# 2019_Dashboard_1-29-19.net
KiCad netlist of a schematic drawn in EAGLE
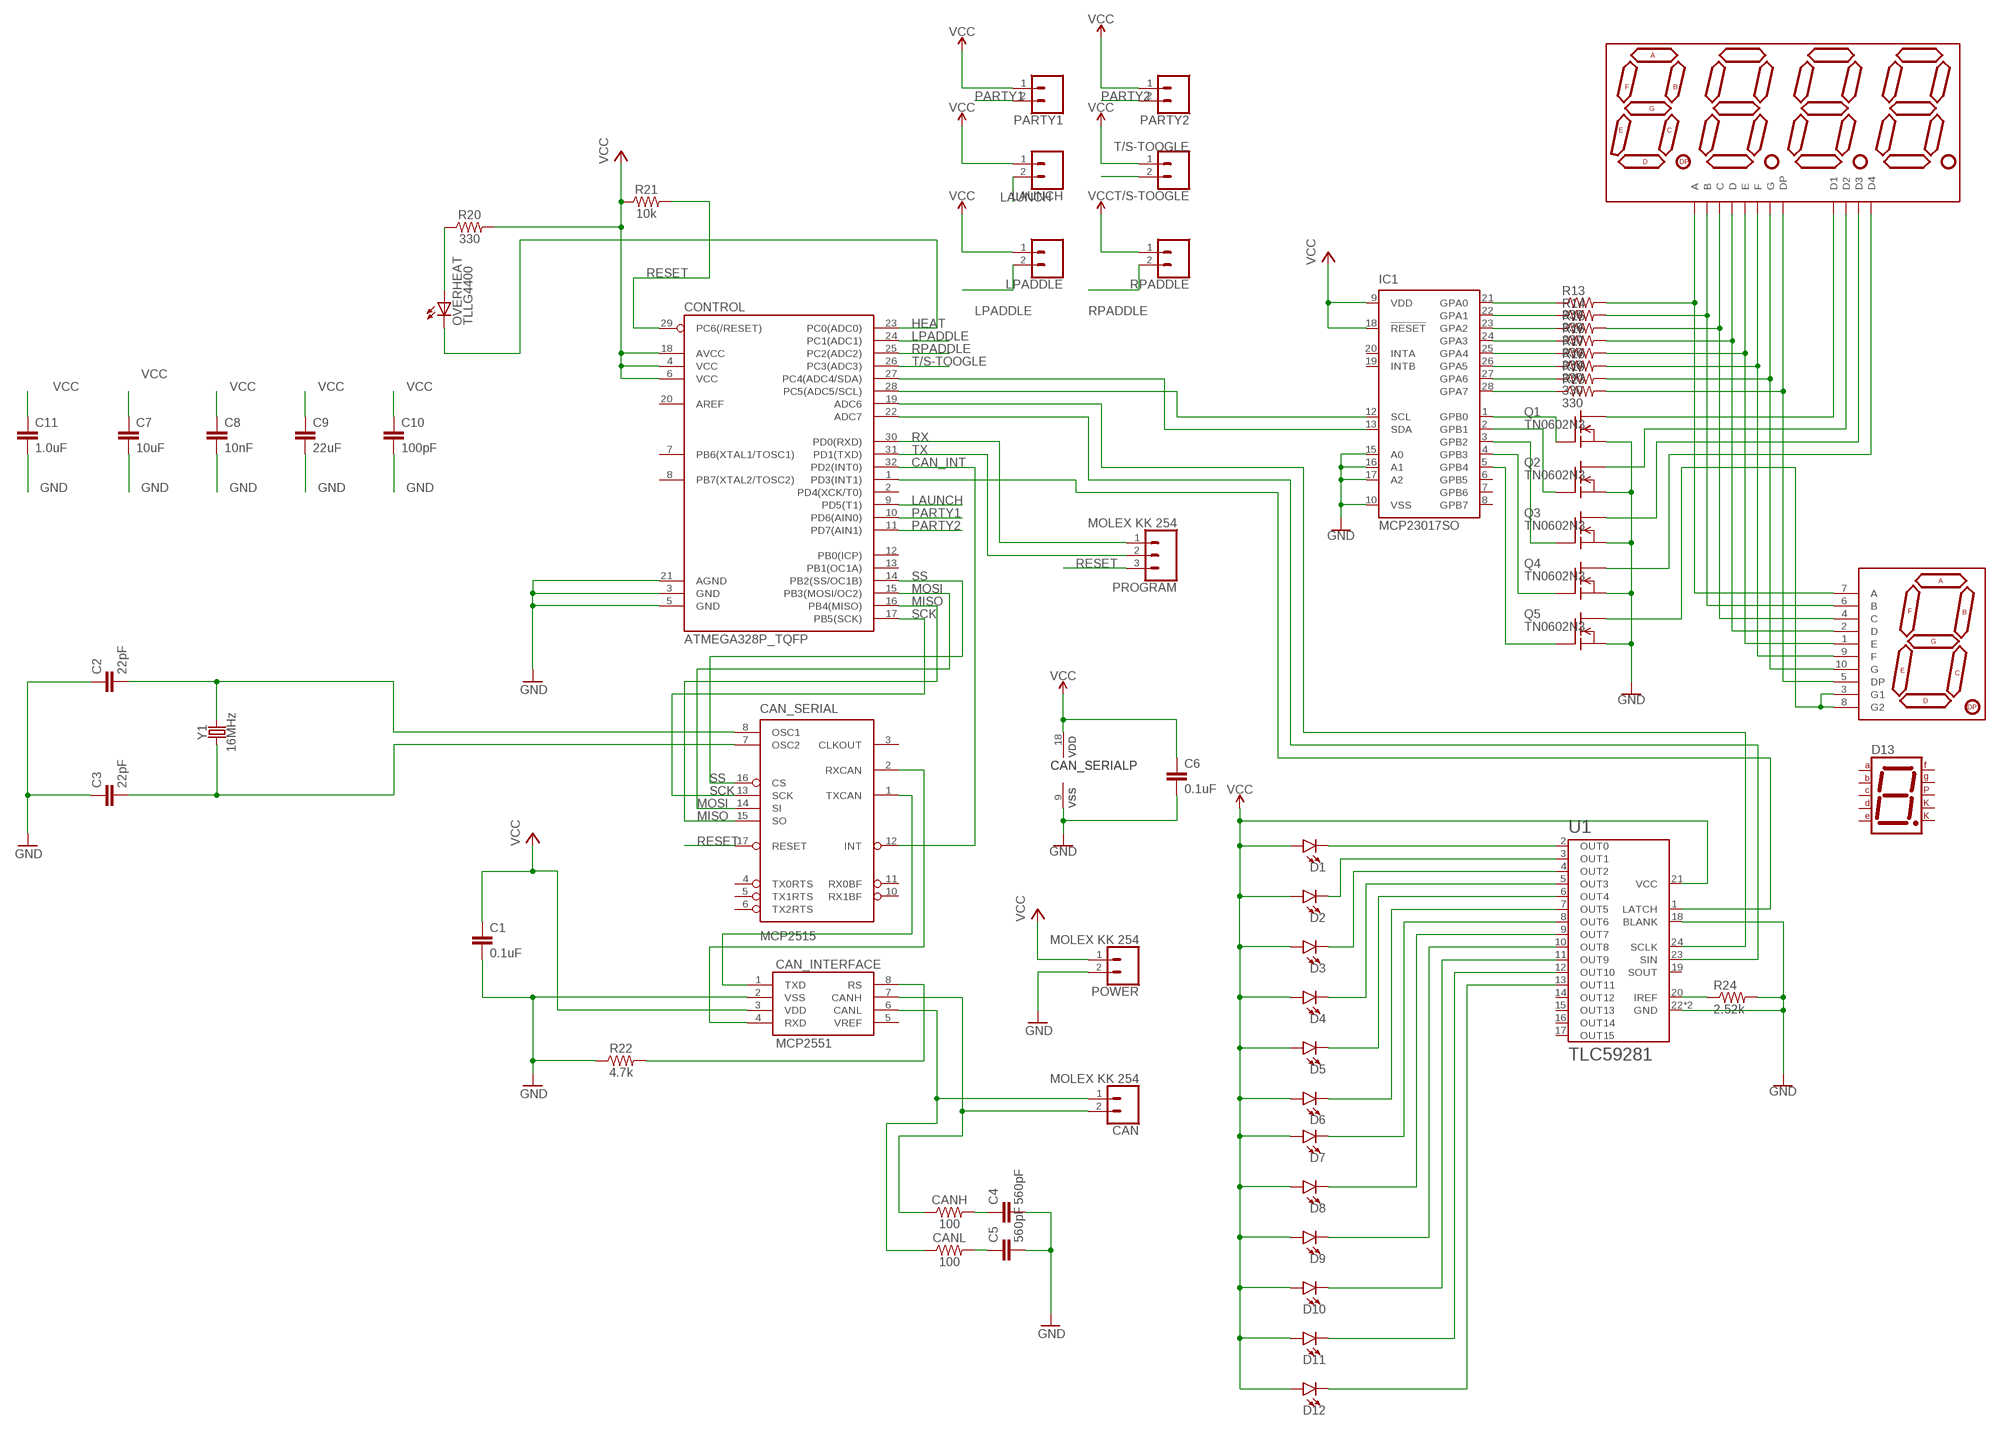
[diagram p0: schematic, sheet 1]

(export (version "E")
  (design (tool "Eeschema 10.0.6"))
  (components
    (comp (ref "C1")
      (value "0.1uF")
      (footprint "eagle-import:0603")
      (libsource (lib "eagle-import") (part "0.1UF-0603-25V-(+80/-20%)"))
    )
    (comp (ref "C2")
      (value "22pF")
      (footprint "eagle-import:0603")
      (libsource (lib "eagle-import") (part "22PF-0603-50V-5%"))
    )
    (comp (ref "C3")
      (value "22pF")
      (footprint "eagle-import:0603")
      (libsource (lib "eagle-import") (part "22PF-0603-50V-5%"))
    )
    (comp (ref "C4")
      (value "560pF")
      (footprint "eagle-import:0603")
      (libsource (lib "eagle-import") (part "560PF-0603-50V-5%"))
    )
    (comp (ref "C5")
      (value "560pF")
      (footprint "eagle-import:0603")
      (libsource (lib "eagle-import") (part "560PF-0603-50V-5%"))
    )
    (comp (ref "C6")
      (value "0.1uF")
      (footprint "eagle-import:0402")
      (libsource (lib "eagle-import") (part "0.1UF-0402-16V-10%"))
    )
    (comp (ref "C7")
      (value "10uF")
      (footprint "eagle-import:0805")
      (libsource (lib "eagle-import") (part "10UF-0805-10V-10%"))
    )
    (comp (ref "C8")
      (value "10nF")
      (footprint "eagle-import:0603")
      (libsource (lib "eagle-import") (part "10NF-0603-50V-10%"))
    )
    (comp (ref "C9")
      (value "22uF")
      (footprint "eagle-import:0805")
      (libsource (lib "eagle-import") (part "22UF-0805-6.3V-20%"))
    )
    (comp (ref "C10")
      (value "100pF")
      (footprint "eagle-import:0603")
      (libsource (lib "eagle-import") (part "100PF-0603-50V-5%"))
    )
    (comp (ref "C11")
      (value "1.0uF")
      (footprint "eagle-import:0805")
      (libsource (lib "eagle-import") (part "1.0UF-0805-25V-(+80/-20%)"))
    )
    (comp (ref "CAN")
      (value "MOLEX KK 254")
      (footprint "eagle-import:1X02")
      (libsource (lib "eagle-import") (part "CONN_02"))
    )
    (comp (ref "CANH")
      (value "100")
      (footprint "eagle-import:0603")
      (libsource (lib "eagle-import") (part "100OHM-0603-1/4W-5%"))
    )
    (comp (ref "CANL")
      (value "100")
      (footprint "eagle-import:0603")
      (libsource (lib "eagle-import") (part "100OHM-0603-1/4W-5%"))
    )
    (comp (ref "CAN_INTERFACE")
      (value "MCP2551")
      (footprint "eagle-import:SO08")
      (libsource (lib "eagle-import") (part "MCP2551"))
    )
    (comp (ref "CAN_SERIAL")
      (value "MCP2515")
      (footprint "eagle-import:SO18W")
      (libsource (lib "eagle-import") (part "MCP2515(MCP2510)SO"))
    )
    (comp (ref "CONTROL")
      (value "ATMEGA328P_TQFP")
      (footprint "eagle-import:TQFP32-08")
      (libsource (lib "eagle-import") (part "ATMEGA328P_TQFP"))
    )
    (comp (ref "D1")
      (value "LED5MM")
      (footprint "eagle-import:LED_5MM")
      (libsource (lib "eagle-import") (part "LED5MM"))
    )
    (comp (ref "D2")
      (value "LED5MM")
      (footprint "eagle-import:LED_5MM")
      (libsource (lib "eagle-import") (part "LED5MM"))
    )
    (comp (ref "D3")
      (value "LED5MM")
      (footprint "eagle-import:LED_5MM")
      (libsource (lib "eagle-import") (part "LED5MM"))
    )
    (comp (ref "D4")
      (value "LED5MM")
      (footprint "eagle-import:LED_5MM")
      (libsource (lib "eagle-import") (part "LED5MM"))
    )
    (comp (ref "D5")
      (value "LED5MM")
      (footprint "eagle-import:LED_5MM")
      (libsource (lib "eagle-import") (part "LED5MM"))
    )
    (comp (ref "D6")
      (value "LED5MM")
      (footprint "eagle-import:LED_5MM")
      (libsource (lib "eagle-import") (part "LED5MM"))
    )
    (comp (ref "D7")
      (value "LED5MM")
      (footprint "eagle-import:LED_5MM")
      (libsource (lib "eagle-import") (part "LED5MM"))
    )
    (comp (ref "D8")
      (value "LED5MM")
      (footprint "eagle-import:LED_5MM")
      (libsource (lib "eagle-import") (part "LED5MM"))
    )
    (comp (ref "D9")
      (value "LED5MM")
      (footprint "eagle-import:LED_5MM")
      (libsource (lib "eagle-import") (part "LED5MM"))
    )
    (comp (ref "D10")
      (value "LED5MM")
      (footprint "eagle-import:LED_5MM")
      (libsource (lib "eagle-import") (part "LED5MM"))
    )
    (comp (ref "D11")
      (value "LED5MM")
      (footprint "eagle-import:LED_5MM")
      (libsource (lib "eagle-import") (part "LED5MM"))
    )
    (comp (ref "D12")
      (value "LED5MM")
      (footprint "eagle-import:LED_5MM")
      (libsource (lib "eagle-import") (part "LED5MM"))
    )
    (comp (ref "D13")
      (value "7SEG-CK")
      (footprint "eagle-import:7SEG-13")
      (libsource (lib "eagle-import") (part "7SEG-CK"))
    )
    (comp (ref "DISP1")
      (value "ATA8041ARBJ")
      (footprint "eagle-import:7-SEGMENT-4DIGIT-20MM")
      (libsource (lib "eagle-import") (part "7-SEGMENT-4DIGIT-20MM-RED"))
    )
    (comp (ref "IC1")
      (value "MCP23017SO")
      (footprint "eagle-import:SO28W")
      (libsource (lib "eagle-import") (part "MCP23017SO"))
    )
    (comp (ref "LAUNCH")
      (value "CONN_02LOCK")
      (footprint "eagle-import:1X02_LOCK")
      (libsource (lib "eagle-import") (part "CONN_02LOCK"))
    )
    (comp (ref "LPADDLE")
      (value "CONN_02LOCK")
      (footprint "eagle-import:1X02_LOCK")
      (libsource (lib "eagle-import") (part "CONN_02LOCK"))
    )
    (comp (ref "OVERHEAT")
      (value "TLLG4400")
      (footprint "eagle-import:LED3MM")
      (fields (field (name "MF") "VISHAY SEMICONDUCTOR"))
      (libsource (lib "eagle-import") (part "TLLG4400"))
    )
    (comp (ref "PARTY1")
      (value "CONN_02LOCK")
      (footprint "eagle-import:1X02_LOCK")
      (libsource (lib "eagle-import") (part "CONN_02LOCK"))
    )
    (comp (ref "PARTY2")
      (value "CONN_02LOCK")
      (footprint "eagle-import:1X02_LOCK")
      (libsource (lib "eagle-import") (part "CONN_02LOCK"))
    )
    (comp (ref "POWER")
      (value "MOLEX KK 254")
      (footprint "eagle-import:1X02")
      (libsource (lib "eagle-import") (part "CONN_02"))
    )
    (comp (ref "PROGRAM")
      (value "MOLEX KK 254")
      (footprint "eagle-import:1X03")
      (libsource (lib "eagle-import") (part "CONN_03"))
    )
    (comp (ref "Q1")
      (value "TN0602N3")
      (footprint "eagle-import:TO-92")
      (libsource (lib "eagle-import") (part "TN0602N3"))
    )
    (comp (ref "Q2")
      (value "TN0602N3")
      (footprint "eagle-import:TO-92")
      (libsource (lib "eagle-import") (part "TN0602N3"))
    )
    (comp (ref "Q3")
      (value "TN0602N3")
      (footprint "eagle-import:TO-92")
      (libsource (lib "eagle-import") (part "TN0602N3"))
    )
    (comp (ref "Q4")
      (value "TN0602N3")
      (footprint "eagle-import:TO-92")
      (libsource (lib "eagle-import") (part "TN0602N3"))
    )
    (comp (ref "Q5")
      (value "TN0602N3")
      (footprint "eagle-import:TO-92")
      (libsource (lib "eagle-import") (part "TN0602N3"))
    )
    (comp (ref "R13")
      (value "330")
      (footprint "eagle-import:R0603")
      (libsource (lib "eagle-import") (part "R-US_R0603"))
    )
    (comp (ref "R14")
      (value "330")
      (footprint "eagle-import:R0603")
      (libsource (lib "eagle-import") (part "R-US_R0603"))
    )
    (comp (ref "R15")
      (value "330")
      (footprint "eagle-import:R0603")
      (libsource (lib "eagle-import") (part "R-US_R0603"))
    )
    (comp (ref "R16")
      (value "330")
      (footprint "eagle-import:R0603")
      (libsource (lib "eagle-import") (part "R-US_R0603"))
    )
    (comp (ref "R17")
      (value "330")
      (footprint "eagle-import:R0603")
      (libsource (lib "eagle-import") (part "R-US_R0603"))
    )
    (comp (ref "R18")
      (value "330")
      (footprint "eagle-import:R0603")
      (libsource (lib "eagle-import") (part "R-US_R0603"))
    )
    (comp (ref "R19")
      (value "330")
      (footprint "eagle-import:R0603")
      (libsource (lib "eagle-import") (part "R-US_R0603"))
    )
    (comp (ref "R20")
      (value "330")
      (footprint "eagle-import:0603")
      (libsource (lib "eagle-import") (part "330OHM-0603-1/10W-1%"))
    )
    (comp (ref "R21")
      (value "10k")
      (footprint "eagle-import:0603")
      (libsource (lib "eagle-import") (part "10KOHM-0603-1/10W-1%"))
    )
    (comp (ref "R22")
      (value "4.7k")
      (footprint "eagle-import:0603")
      (libsource (lib "eagle-import") (part "4.7KOHM-0603-1/10W-1%"))
    )
    (comp (ref "R23")
      (value "330")
      (footprint "eagle-import:R0603")
      (libsource (lib "eagle-import") (part "R-US_R0603"))
    )
    (comp (ref "R24")
      (value "2.52k")
      (footprint "eagle-import:R0603")
      (libsource (lib "eagle-import") (part "R-US_R0603"))
    )
    (comp (ref "RPADDLE")
      (value "CONN_02LOCK")
      (footprint "eagle-import:1X02_LOCK")
      (libsource (lib "eagle-import") (part "CONN_02LOCK"))
    )
    (comp (ref "T/S-TOOGLE")
      (value "CONN_02LOCK")
      (footprint "eagle-import:1X02_LOCK")
      (libsource (lib "eagle-import") (part "CONN_02LOCK"))
    )
    (comp (ref "U$1")
      (value "YSD-1601AR4B-8")
      (footprint "eagle-import:7-SEGMENT-1_PTH")
      (libsource (lib "eagle-import") (part "7-SEGMENT-1DIGIT-1INCH-RED"))
    )
    (comp (ref "U1")
      (value "TLC59281")
      (footprint "eagle-import:QFN-24")
      (fields (field (name "MF") "Texas Instruments"))
      (libsource (lib "eagle-import") (part "TLC59281"))
    )
    (comp (ref "Y1")
      (value "16MHz")
      (footprint "eagle-import:HC49US")
      (libsource (lib "eagle-import") (part "CRYSTAL-16MHZPTH-HC49US"))
    )
  )
  (nets
    (net (code "1") (name "/CAN_INT") (class "Default")
      (node (ref "CAN_SERIAL") (pin "12") (pinfunction "INT_12") (pintype "output"))
      (node (ref "CONTROL") (pin "32") (pinfunction "PD2(INT0)_32") (pintype "bidirectional"))
    )
    (net (code "2") (name "/HEAT") (class "Default")
      (node (ref "CONTROL") (pin "23") (pinfunction "PC0(ADC0)_23") (pintype "bidirectional"))
      (node (ref "OVERHEAT") (pin "K") (pinfunction "C_K") (pintype "passive"))
    )
    (net (code "3") (name "/LAUNCH") (class "Default")
      (node (ref "CONTROL") (pin "9") (pinfunction "PD5(T1)_9") (pintype "bidirectional"))
      (node (ref "LAUNCH") (pin "2") (pinfunction "2_2") (pintype "passive"))
    )
    (net (code "4") (name "/LPADDLE") (class "Default")
      (node (ref "CONTROL") (pin "24") (pinfunction "PC1(ADC1)_24") (pintype "bidirectional"))
      (node (ref "LPADDLE") (pin "2") (pinfunction "2_2") (pintype "passive"))
    )
    (net (code "5") (name "/MISO") (class "Default")
      (node (ref "CAN_SERIAL") (pin "15") (pinfunction "SO_15") (pintype "output"))
      (node (ref "CONTROL") (pin "16") (pinfunction "PB4(MISO)_16") (pintype "bidirectional"))
    )
    (net (code "6") (name "/MOSI") (class "Default")
      (node (ref "CAN_SERIAL") (pin "14") (pinfunction "SI_14") (pintype "input"))
      (node (ref "CONTROL") (pin "15") (pinfunction "PB3(MOSI/OC2)_15") (pintype "bidirectional"))
    )
    (net (code "7") (name "/PARTY1") (class "Default")
      (node (ref "CONTROL") (pin "10") (pinfunction "PD6(AIN0)_10") (pintype "bidirectional"))
      (node (ref "PARTY1") (pin "2") (pinfunction "2_2") (pintype "passive"))
    )
    (net (code "8") (name "/PARTY2") (class "Default")
      (node (ref "CONTROL") (pin "11") (pinfunction "PD7(AIN1)_11") (pintype "bidirectional"))
      (node (ref "PARTY2") (pin "2") (pinfunction "2_2") (pintype "passive"))
    )
    (net (code "9") (name "/RESET") (class "Default")
      (node (ref "CAN_SERIAL") (pin "17") (pinfunction "RESET_17") (pintype "input"))
      (node (ref "CONTROL") (pin "29") (pinfunction "PC6(/RESET)_29") (pintype "bidirectional"))
      (node (ref "PROGRAM") (pin "3") (pinfunction "3_3") (pintype "passive"))
      (node (ref "R21") (pin "2") (pinfunction "2_2") (pintype "passive"))
    )
    (net (code "10") (name "/RPADDLE") (class "Default")
      (node (ref "CONTROL") (pin "25") (pinfunction "PC2(ADC2)_25") (pintype "bidirectional"))
      (node (ref "RPADDLE") (pin "2") (pinfunction "2_2") (pintype "passive"))
    )
    (net (code "11") (name "/RX") (class "Default")
      (node (ref "CONTROL") (pin "30") (pinfunction "PD0(RXD)_30") (pintype "bidirectional"))
      (node (ref "PROGRAM") (pin "1") (pinfunction "1_1") (pintype "passive"))
    )
    (net (code "12") (name "/SCK") (class "Default")
      (node (ref "CAN_SERIAL") (pin "13") (pinfunction "SCK_13") (pintype "input"))
      (node (ref "CONTROL") (pin "17") (pinfunction "PB5(SCK)_17") (pintype "bidirectional"))
    )
    (net (code "13") (name "/SS") (class "Default")
      (node (ref "CAN_SERIAL") (pin "16") (pinfunction "CS_16") (pintype "input"))
      (node (ref "CONTROL") (pin "14") (pinfunction "PB2(SS/OC1B)_14") (pintype "bidirectional"))
    )
    (net (code "14") (name "/TX") (class "Default")
      (node (ref "CONTROL") (pin "31") (pinfunction "PD1(TXD)_31") (pintype "bidirectional"))
      (node (ref "PROGRAM") (pin "2") (pinfunction "2_2") (pintype "passive"))
    )
    (net (code "15") (name "/T{slash}S-TOOGLE") (class "Default")
      (node (ref "CONTROL") (pin "26") (pinfunction "PC3(ADC3)_26") (pintype "bidirectional"))
      (node (ref "T/S-TOOGLE") (pin "2") (pinfunction "2_2") (pintype "passive"))
    )
    (net (code "16") (name "GND") (class "Default")
      (node (ref "C1") (pin "2") (pinfunction "2_2") (pintype "passive"))
      (node (ref "C10") (pin "2") (pinfunction "2_2") (pintype "passive"))
      (node (ref "C11") (pin "2") (pinfunction "2_2") (pintype "passive"))
      (node (ref "C2") (pin "1") (pinfunction "1_1") (pintype "passive"))
      (node (ref "C3") (pin "1") (pinfunction "1_1") (pintype "passive"))
      (node (ref "C4") (pin "2") (pinfunction "2_2") (pintype "passive"))
      (node (ref "C5") (pin "2") (pinfunction "2_2") (pintype "passive"))
      (node (ref "C6") (pin "2") (pinfunction "2_2") (pintype "passive"))
      (node (ref "C7") (pin "2") (pinfunction "2_2") (pintype "passive"))
      (node (ref "C8") (pin "2") (pinfunction "2_2") (pintype "passive"))
      (node (ref "C9") (pin "2") (pinfunction "2_2") (pintype "passive"))
      (node (ref "CAN_INTERFACE") (pin "2") (pinfunction "VSS_2") (pintype "bidirectional"))
      (node (ref "CAN_SERIAL") (pin "9") (pinfunction "VSS_9") (pintype "power_in"))
      (node (ref "CONTROL") (pin "21") (pinfunction "AGND_21") (pintype "bidirectional"))
      (node (ref "CONTROL") (pin "3") (pinfunction "GND_3") (pintype "bidirectional"))
      (node (ref "CONTROL") (pin "5") (pinfunction "GND_5") (pintype "bidirectional"))
      (node (ref "IC1") (pin "10") (pinfunction "VSS_10") (pintype "power_in"))
      (node (ref "IC1") (pin "15") (pinfunction "A0_15") (pintype "input"))
      (node (ref "IC1") (pin "16") (pinfunction "A1_16") (pintype "input"))
      (node (ref "IC1") (pin "17") (pinfunction "A2_17") (pintype "input"))
      (node (ref "POWER") (pin "2") (pinfunction "2_2") (pintype "passive"))
      (node (ref "Q1") (pin "1") (pinfunction "S_1") (pintype "passive"))
      (node (ref "Q2") (pin "1") (pinfunction "S_1") (pintype "passive"))
      (node (ref "Q3") (pin "1") (pinfunction "S_1") (pintype "passive"))
      (node (ref "Q4") (pin "1") (pinfunction "S_1") (pintype "passive"))
      (node (ref "Q5") (pin "1") (pinfunction "S_1") (pintype "passive"))
      (node (ref "R22") (pin "1") (pinfunction "1_1") (pintype "passive"))
      (node (ref "R24") (pin "2") (pinfunction "2_2") (pintype "passive"))
      (node (ref "U1") (pin "18") (pinfunction "BLANK_18") (pintype "bidirectional"))
      (node (ref "U1") (pin "22") (pinfunction "GND_22") (pintype "bidirectional"))
      (node (ref "U1") (pin "EP") (pinfunction "GND_EP") (pintype "bidirectional"))
    )
    (net (code "17") (name "Net-(C4-Pad1)") (class "Default")
      (node (ref "C4") (pin "1") (pinfunction "1_1") (pintype "passive"))
      (node (ref "CANH") (pin "2") (pinfunction "2_2") (pintype "passive"))
    )
    (net (code "18") (name "Net-(C5-Pad1)") (class "Default")
      (node (ref "C5") (pin "1") (pinfunction "1_1") (pintype "passive"))
      (node (ref "CANL") (pin "2") (pinfunction "2_2") (pintype "passive"))
    )
    (net (code "19") (name "Net-(CAN_INTERFACE-CANH)") (class "Default")
      (node (ref "CAN") (pin "2") (pinfunction "2_2") (pintype "passive"))
      (node (ref "CANH") (pin "1") (pinfunction "1_1") (pintype "passive"))
      (node (ref "CAN_INTERFACE") (pin "7") (pinfunction "CANH_7") (pintype "bidirectional"))
    )
    (net (code "20") (name "Net-(CAN_INTERFACE-CANL)") (class "Default")
      (node (ref "CAN") (pin "1") (pinfunction "1_1") (pintype "passive"))
      (node (ref "CANL") (pin "1") (pinfunction "1_1") (pintype "passive"))
      (node (ref "CAN_INTERFACE") (pin "6") (pinfunction "CANL_6") (pintype "bidirectional"))
    )
    (net (code "21") (name "Net-(CAN_INTERFACE-RS)") (class "Default")
      (node (ref "CAN_INTERFACE") (pin "8") (pinfunction "RS_8") (pintype "bidirectional"))
      (node (ref "R22") (pin "2") (pinfunction "2_2") (pintype "passive"))
    )
    (net (code "22") (name "Net-(CAN_INTERFACE-RXD)") (class "Default")
      (node (ref "CAN_INTERFACE") (pin "4") (pinfunction "RXD_4") (pintype "bidirectional"))
      (node (ref "CAN_SERIAL") (pin "2") (pinfunction "RXCAN_2") (pintype "input"))
    )
    (net (code "23") (name "Net-(CAN_INTERFACE-TXD)") (class "Default")
      (node (ref "CAN_INTERFACE") (pin "1") (pinfunction "TXD_1") (pintype "bidirectional"))
      (node (ref "CAN_SERIAL") (pin "1") (pinfunction "TXCAN_1") (pintype "output"))
    )
    (net (code "24") (name "Net-(CAN_SERIALA-OSC1)") (class "Default")
      (node (ref "C2") (pin "2") (pinfunction "2_2") (pintype "passive"))
      (node (ref "CAN_SERIAL") (pin "8") (pinfunction "OSC1_8") (pintype "input"))
      (node (ref "Y1") (pin "2") (pinfunction "2_2") (pintype "passive"))
    )
    (net (code "25") (name "Net-(CAN_SERIALA-OSC2)") (class "Default")
      (node (ref "C3") (pin "2") (pinfunction "2_2") (pintype "passive"))
      (node (ref "CAN_SERIAL") (pin "7") (pinfunction "OSC2_7") (pintype "output"))
      (node (ref "Y1") (pin "1") (pinfunction "1_1") (pintype "passive"))
    )
    (net (code "26") (name "Net-(CONTROL-ADC6)") (class "Default")
      (node (ref "CONTROL") (pin "19") (pinfunction "ADC6_19") (pintype "bidirectional"))
      (node (ref "U1") (pin "24") (pinfunction "SCLK_24") (pintype "bidirectional"))
    )
    (net (code "27") (name "Net-(CONTROL-ADC7)") (class "Default")
      (node (ref "CONTROL") (pin "22") (pinfunction "ADC7_22") (pintype "bidirectional"))
      (node (ref "U1") (pin "23") (pinfunction "SIN_23") (pintype "bidirectional"))
    )
    (net (code "28") (name "Net-(CONTROL-PC4(ADC4{slash}SDA))") (class "Default")
      (node (ref "CONTROL") (pin "27") (pinfunction "PC4(ADC4/SDA)_27") (pintype "bidirectional"))
      (node (ref "IC1") (pin "13") (pinfunction "SDA_13") (pintype "bidirectional"))
    )
    (net (code "29") (name "Net-(CONTROL-PC5(ADC5{slash}SCL))") (class "Default")
      (node (ref "CONTROL") (pin "28") (pinfunction "PC5(ADC5/SCL)_28") (pintype "bidirectional"))
      (node (ref "IC1") (pin "12") (pinfunction "SCL_12") (pintype "input"))
    )
    (net (code "30") (name "Net-(CONTROL-PD3(INT1))") (class "Default")
      (node (ref "CONTROL") (pin "1") (pinfunction "PD3(INT1)_1") (pintype "bidirectional"))
      (node (ref "U1") (pin "1") (pinfunction "LATCH_1") (pintype "bidirectional"))
    )
    (net (code "31") (name "Net-(D1-C)") (class "Default")
      (node (ref "D1") (pin "K") (pinfunction "C_K") (pintype "passive"))
      (node (ref "U1") (pin "2") (pinfunction "OUT0_2") (pintype "bidirectional"))
    )
    (net (code "32") (name "Net-(D2-C)") (class "Default")
      (node (ref "D2") (pin "K") (pinfunction "C_K") (pintype "passive"))
      (node (ref "U1") (pin "3") (pinfunction "OUT1_3") (pintype "bidirectional"))
    )
    (net (code "33") (name "Net-(D3-C)") (class "Default")
      (node (ref "D3") (pin "K") (pinfunction "C_K") (pintype "passive"))
      (node (ref "U1") (pin "4") (pinfunction "OUT2_4") (pintype "bidirectional"))
    )
    (net (code "34") (name "Net-(D4-C)") (class "Default")
      (node (ref "D4") (pin "K") (pinfunction "C_K") (pintype "passive"))
      (node (ref "U1") (pin "5") (pinfunction "OUT3_5") (pintype "bidirectional"))
    )
    (net (code "35") (name "Net-(D5-C)") (class "Default")
      (node (ref "D5") (pin "K") (pinfunction "C_K") (pintype "passive"))
      (node (ref "U1") (pin "6") (pinfunction "OUT4_6") (pintype "bidirectional"))
    )
    (net (code "36") (name "Net-(D6-C)") (class "Default")
      (node (ref "D6") (pin "K") (pinfunction "C_K") (pintype "passive"))
      (node (ref "U1") (pin "7") (pinfunction "OUT5_7") (pintype "bidirectional"))
    )
    (net (code "37") (name "Net-(D7-C)") (class "Default")
      (node (ref "D7") (pin "K") (pinfunction "C_K") (pintype "passive"))
      (node (ref "U1") (pin "8") (pinfunction "OUT6_8") (pintype "bidirectional"))
    )
    (net (code "38") (name "Net-(D8-C)") (class "Default")
      (node (ref "D8") (pin "K") (pinfunction "C_K") (pintype "passive"))
      (node (ref "U1") (pin "9") (pinfunction "OUT7_9") (pintype "bidirectional"))
    )
    (net (code "39") (name "Net-(D9-C)") (class "Default")
      (node (ref "D9") (pin "K") (pinfunction "C_K") (pintype "passive"))
      (node (ref "U1") (pin "10") (pinfunction "OUT8_10") (pintype "bidirectional"))
    )
    (net (code "40") (name "Net-(D10-C)") (class "Default")
      (node (ref "D10") (pin "K") (pinfunction "C_K") (pintype "passive"))
      (node (ref "U1") (pin "11") (pinfunction "OUT9_11") (pintype "bidirectional"))
    )
    (net (code "41") (name "Net-(D11-C)") (class "Default")
      (node (ref "D11") (pin "K") (pinfunction "C_K") (pintype "passive"))
      (node (ref "U1") (pin "12") (pinfunction "OUT10_12") (pintype "bidirectional"))
    )
    (net (code "42") (name "Net-(D12-C)") (class "Default")
      (node (ref "D12") (pin "K") (pinfunction "C_K") (pintype "passive"))
      (node (ref "U1") (pin "13") (pinfunction "OUT11_13") (pintype "bidirectional"))
    )
    (net (code "43") (name "Net-(DISP1-A)") (class "Default")
      (node (ref "DISP1") (pin "11") (pinfunction "A_11") (pintype "bidirectional"))
      (node (ref "R13") (pin "2") (pinfunction "2_2") (pintype "passive"))
      (node (ref "U$1") (pin "7") (pinfunction "A_7") (pintype "bidirectional"))
    )
    (net (code "44") (name "Net-(DISP1-B)") (class "Default")
      (node (ref "DISP1") (pin "7") (pinfunction "B_7") (pintype "bidirectional"))
      (node (ref "R14") (pin "2") (pinfunction "2_2") (pintype "passive"))
      (node (ref "U$1") (pin "6") (pinfunction "B_6") (pintype "bidirectional"))
    )
    (net (code "45") (name "Net-(DISP1-C)") (class "Default")
      (node (ref "DISP1") (pin "4") (pinfunction "C_4") (pintype "bidirectional"))
      (node (ref "R15") (pin "2") (pinfunction "2_2") (pintype "passive"))
      (node (ref "U$1") (pin "4") (pinfunction "C_4") (pintype "bidirectional"))
    )
    (net (code "46") (name "Net-(DISP1-D)") (class "Default")
      (node (ref "DISP1") (pin "2") (pinfunction "D_2") (pintype "bidirectional"))
      (node (ref "R16") (pin "2") (pinfunction "2_2") (pintype "passive"))
      (node (ref "U$1") (pin "2") (pinfunction "D_2") (pintype "bidirectional"))
    )
    (net (code "47") (name "Net-(DISP1-D1)") (class "Default")
      (node (ref "DISP1") (pin "12") (pinfunction "D1_12") (pintype "bidirectional"))
      (node (ref "Q1") (pin "3") (pinfunction "D_3") (pintype "passive"))
    )
    (net (code "48") (name "Net-(DISP1-D2)") (class "Default")
      (node (ref "DISP1") (pin "9") (pinfunction "D2_9") (pintype "bidirectional"))
      (node (ref "Q2") (pin "3") (pinfunction "D_3") (pintype "passive"))
    )
    (net (code "49") (name "Net-(DISP1-D3)") (class "Default")
      (node (ref "DISP1") (pin "8") (pinfunction "D3_8") (pintype "bidirectional"))
      (node (ref "Q3") (pin "3") (pinfunction "D_3") (pintype "passive"))
    )
    (net (code "50") (name "Net-(DISP1-D4)") (class "Default")
      (node (ref "DISP1") (pin "6") (pinfunction "D4_6") (pintype "bidirectional"))
      (node (ref "Q4") (pin "3") (pinfunction "D_3") (pintype "passive"))
    )
    (net (code "51") (name "Net-(DISP1-DP)") (class "Default")
      (node (ref "DISP1") (pin "3") (pinfunction "DP_3") (pintype "bidirectional"))
      (node (ref "R23") (pin "2") (pinfunction "2_2") (pintype "passive"))
      (node (ref "U$1") (pin "5") (pinfunction "DP_5") (pintype "bidirectional"))
    )
    (net (code "52") (name "Net-(DISP1-E)") (class "Default")
      (node (ref "DISP1") (pin "1") (pinfunction "E_1") (pintype "bidirectional"))
      (node (ref "R17") (pin "2") (pinfunction "2_2") (pintype "passive"))
      (node (ref "U$1") (pin "1") (pinfunction "E_1") (pintype "bidirectional"))
    )
    (net (code "53") (name "Net-(DISP1-F)") (class "Default")
      (node (ref "DISP1") (pin "10") (pinfunction "F_10") (pintype "bidirectional"))
      (node (ref "R18") (pin "2") (pinfunction "2_2") (pintype "passive"))
      (node (ref "U$1") (pin "9") (pinfunction "F_9") (pintype "bidirectional"))
    )
    (net (code "54") (name "Net-(DISP1-G)") (class "Default")
      (node (ref "DISP1") (pin "5") (pinfunction "G_5") (pintype "bidirectional"))
      (node (ref "R19") (pin "2") (pinfunction "2_2") (pintype "passive"))
      (node (ref "U$1") (pin "10") (pinfunction "G_10") (pintype "bidirectional"))
    )
    (net (code "55") (name "Net-(IC1-GPA0)") (class "Default")
      (node (ref "IC1") (pin "21") (pinfunction "GPA0_21") (pintype "bidirectional"))
      (node (ref "R13") (pin "1") (pinfunction "1_1") (pintype "passive"))
    )
    (net (code "56") (name "Net-(IC1-GPA1)") (class "Default")
      (node (ref "IC1") (pin "22") (pinfunction "GPA1_22") (pintype "bidirectional"))
      (node (ref "R14") (pin "1") (pinfunction "1_1") (pintype "passive"))
    )
    (net (code "57") (name "Net-(IC1-GPA2)") (class "Default")
      (node (ref "IC1") (pin "23") (pinfunction "GPA2_23") (pintype "bidirectional"))
      (node (ref "R15") (pin "1") (pinfunction "1_1") (pintype "passive"))
    )
    (net (code "58") (name "Net-(IC1-GPA3)") (class "Default")
      (node (ref "IC1") (pin "24") (pinfunction "GPA3_24") (pintype "bidirectional"))
      (node (ref "R16") (pin "1") (pinfunction "1_1") (pintype "passive"))
    )
    (net (code "59") (name "Net-(IC1-GPA4)") (class "Default")
      (node (ref "IC1") (pin "25") (pinfunction "GPA4_25") (pintype "bidirectional"))
      (node (ref "R17") (pin "1") (pinfunction "1_1") (pintype "passive"))
    )
    (net (code "60") (name "Net-(IC1-GPA5)") (class "Default")
      (node (ref "IC1") (pin "26") (pinfunction "GPA5_26") (pintype "bidirectional"))
      (node (ref "R18") (pin "1") (pinfunction "1_1") (pintype "passive"))
    )
    (net (code "61") (name "Net-(IC1-GPA6)") (class "Default")
      (node (ref "IC1") (pin "27") (pinfunction "GPA6_27") (pintype "bidirectional"))
      (node (ref "R19") (pin "1") (pinfunction "1_1") (pintype "passive"))
    )
    (net (code "62") (name "Net-(IC1-GPA7)") (class "Default")
      (node (ref "IC1") (pin "28") (pinfunction "GPA7_28") (pintype "bidirectional"))
      (node (ref "R23") (pin "1") (pinfunction "1_1") (pintype "passive"))
    )
    (net (code "63") (name "Net-(IC1-GPB0)") (class "Default")
      (node (ref "IC1") (pin "1") (pinfunction "GPB0_1") (pintype "bidirectional"))
      (node (ref "Q1") (pin "2") (pinfunction "G_2") (pintype "passive"))
    )
    (net (code "64") (name "Net-(IC1-GPB1)") (class "Default")
      (node (ref "IC1") (pin "2") (pinfunction "GPB1_2") (pintype "bidirectional"))
      (node (ref "Q2") (pin "2") (pinfunction "G_2") (pintype "passive"))
    )
    (net (code "65") (name "Net-(IC1-GPB2)") (class "Default")
      (node (ref "IC1") (pin "3") (pinfunction "GPB2_3") (pintype "bidirectional"))
      (node (ref "Q3") (pin "2") (pinfunction "G_2") (pintype "passive"))
    )
    (net (code "66") (name "Net-(IC1-GPB3)") (class "Default")
      (node (ref "IC1") (pin "4") (pinfunction "GPB3_4") (pintype "bidirectional"))
      (node (ref "Q4") (pin "2") (pinfunction "G_2") (pintype "passive"))
    )
    (net (code "67") (name "Net-(IC1-GPB4)") (class "Default")
      (node (ref "IC1") (pin "5") (pinfunction "GPB4_5") (pintype "bidirectional"))
      (node (ref "Q5") (pin "2") (pinfunction "G_2") (pintype "passive"))
    )
    (net (code "68") (name "Net-(OVERHEAT-PadA)") (class "Default")
      (node (ref "OVERHEAT") (pin "A") (pinfunction "A_A") (pintype "passive"))
      (node (ref "R20") (pin "1") (pinfunction "1_1") (pintype "passive"))
    )
    (net (code "69") (name "Net-(Q5-D)") (class "Default")
      (node (ref "Q5") (pin "3") (pinfunction "D_3") (pintype "passive"))
      (node (ref "U$1") (pin "3") (pinfunction "G1_3") (pintype "bidirectional"))
      (node (ref "U$1") (pin "8") (pinfunction "G2_8") (pintype "bidirectional"))
    )
    (net (code "70") (name "Net-(U1-IREF)") (class "Default")
      (node (ref "R24") (pin "1") (pinfunction "1_1") (pintype "passive"))
      (node (ref "U1") (pin "20") (pinfunction "IREF_20") (pintype "bidirectional"))
    )
    (net (code "71") (name "VCC") (class "Default")
      (node (ref "C1") (pin "1") (pinfunction "1_1") (pintype "passive"))
      (node (ref "C10") (pin "1") (pinfunction "1_1") (pintype "passive"))
      (node (ref "C11") (pin "1") (pinfunction "1_1") (pintype "passive"))
      (node (ref "C6") (pin "1") (pinfunction "1_1") (pintype "passive"))
      (node (ref "C7") (pin "1") (pinfunction "1_1") (pintype "passive"))
      (node (ref "C8") (pin "1") (pinfunction "1_1") (pintype "passive"))
      (node (ref "C9") (pin "1") (pinfunction "1_1") (pintype "passive"))
      (node (ref "CAN_INTERFACE") (pin "3") (pinfunction "VDD_3") (pintype "bidirectional"))
      (node (ref "CAN_SERIAL") (pin "18") (pinfunction "VDD_18") (pintype "power_in"))
      (node (ref "CONTROL") (pin "18") (pinfunction "AVCC_18") (pintype "bidirectional"))
      (node (ref "CONTROL") (pin "4") (pinfunction "VCC_4") (pintype "bidirectional"))
      (node (ref "CONTROL") (pin "6") (pinfunction "VCC_6") (pintype "bidirectional"))
      (node (ref "D1") (pin "A") (pinfunction "A_A") (pintype "passive"))
      (node (ref "D10") (pin "A") (pinfunction "A_A") (pintype "passive"))
      (node (ref "D11") (pin "A") (pinfunction "A_A") (pintype "passive"))
      (node (ref "D12") (pin "A") (pinfunction "A_A") (pintype "passive"))
      (node (ref "D2") (pin "A") (pinfunction "A_A") (pintype "passive"))
      (node (ref "D3") (pin "A") (pinfunction "A_A") (pintype "passive"))
      (node (ref "D4") (pin "A") (pinfunction "A_A") (pintype "passive"))
      (node (ref "D5") (pin "A") (pinfunction "A_A") (pintype "passive"))
      (node (ref "D6") (pin "A") (pinfunction "A_A") (pintype "passive"))
      (node (ref "D7") (pin "A") (pinfunction "A_A") (pintype "passive"))
      (node (ref "D8") (pin "A") (pinfunction "A_A") (pintype "passive"))
      (node (ref "D9") (pin "A") (pinfunction "A_A") (pintype "passive"))
      (node (ref "IC1") (pin "18") (pinfunction "~{RESET}_18") (pintype "input"))
      (node (ref "IC1") (pin "9") (pinfunction "VDD_9") (pintype "power_in"))
      (node (ref "LAUNCH") (pin "1") (pinfunction "1_1") (pintype "passive"))
      (node (ref "LPADDLE") (pin "1") (pinfunction "1_1") (pintype "passive"))
      (node (ref "PARTY1") (pin "1") (pinfunction "1_1") (pintype "passive"))
      (node (ref "PARTY2") (pin "1") (pinfunction "1_1") (pintype "passive"))
      (node (ref "POWER") (pin "1") (pinfunction "1_1") (pintype "passive"))
      (node (ref "R20") (pin "2") (pinfunction "2_2") (pintype "passive"))
      (node (ref "R21") (pin "1") (pinfunction "1_1") (pintype "passive"))
      (node (ref "RPADDLE") (pin "1") (pinfunction "1_1") (pintype "passive"))
      (node (ref "T/S-TOOGLE") (pin "1") (pinfunction "1_1") (pintype "passive"))
      (node (ref "U1") (pin "21") (pinfunction "VCC_21") (pintype "bidirectional"))
    )
    (net (code "72") (name "unconnected-(CAN_INTERFACE-VREF-Pad5)") (class "Default")
      (node (ref "CAN_INTERFACE") (pin "5") (pinfunction "VREF_5") (pintype "bidirectional"))
    )
    (net (code "73") (name "unconnected-(CAN_SERIALA-CLKOUT-Pad3)") (class "Default")
      (node (ref "CAN_SERIAL") (pin "3") (pinfunction "CLKOUT_3") (pintype "output"))
    )
    (net (code "74") (name "unconnected-(CAN_SERIALA-RX0BF-Pad11)") (class "Default")
      (node (ref "CAN_SERIAL") (pin "11") (pinfunction "RX0BF_11") (pintype "output"))
    )
    (net (code "75") (name "unconnected-(CAN_SERIALA-RX1BF-Pad10)") (class "Default")
      (node (ref "CAN_SERIAL") (pin "10") (pinfunction "RX1BF_10") (pintype "output"))
    )
    (net (code "76") (name "unconnected-(CAN_SERIALA-TX0RTS-Pad4)") (class "Default")
      (node (ref "CAN_SERIAL") (pin "4") (pinfunction "TX0RTS_4") (pintype "input"))
    )
    (net (code "77") (name "unconnected-(CAN_SERIALA-TX1RTS-Pad5)") (class "Default")
      (node (ref "CAN_SERIAL") (pin "5") (pinfunction "TX1RTS_5") (pintype "input"))
    )
    (net (code "78") (name "unconnected-(CAN_SERIALA-TX2RTS-Pad6)") (class "Default")
      (node (ref "CAN_SERIAL") (pin "6") (pinfunction "TX2RTS_6") (pintype "input"))
    )
    (net (code "79") (name "unconnected-(CONTROL-AREF-Pad20)") (class "Default")
      (node (ref "CONTROL") (pin "20") (pinfunction "AREF_20") (pintype "bidirectional"))
    )
    (net (code "80") (name "unconnected-(CONTROL-PB0(ICP)-Pad12)") (class "Default")
      (node (ref "CONTROL") (pin "12") (pinfunction "PB0(ICP)_12") (pintype "bidirectional"))
    )
    (net (code "81") (name "unconnected-(CONTROL-PB1(OC1A)-Pad13)") (class "Default")
      (node (ref "CONTROL") (pin "13") (pinfunction "PB1(OC1A)_13") (pintype "bidirectional"))
    )
    (net (code "82") (name "unconnected-(CONTROL-PB6(XTAL1{slash}TOSC1)-Pad7)") (class "Default")
      (node (ref "CONTROL") (pin "7") (pinfunction "PB6(XTAL1/TOSC1)_7") (pintype "bidirectional"))
    )
    (net (code "83") (name "unconnected-(CONTROL-PB7(XTAL2{slash}TOSC2)-Pad8)") (class "Default")
      (node (ref "CONTROL") (pin "8") (pinfunction "PB7(XTAL2/TOSC2)_8") (pintype "bidirectional"))
    )
    (net (code "84") (name "unconnected-(CONTROL-PD4(XCK{slash}T0)-Pad2)") (class "Default")
      (node (ref "CONTROL") (pin "2") (pinfunction "PD4(XCK/T0)_2") (pintype "bidirectional"))
    )
    (net (code "85") (name "unconnected-(D13-A-Pad7)") (class "Default")
      (node (ref "D13") (pin "7") (pinfunction "A_7") (pintype "passive"))
    )
    (net (code "86") (name "unconnected-(D13-B-Pad6)") (class "Default")
      (node (ref "D13") (pin "6") (pinfunction "B_6") (pintype "passive"))
    )
    (net (code "87") (name "unconnected-(D13-C-Pad4)") (class "Default")
      (node (ref "D13") (pin "4") (pinfunction "C_4") (pintype "passive"))
    )
    (net (code "88") (name "unconnected-(D13-CK1-Pad3)") (class "Default")
      (node (ref "D13") (pin "3") (pinfunction "CK1_3") (pintype "passive"))
    )
    (net (code "89") (name "unconnected-(D13-CK2-Pad8)") (class "Default")
      (node (ref "D13") (pin "8") (pinfunction "CK2_8") (pintype "passive"))
    )
    (net (code "90") (name "unconnected-(D13-D-Pad2)") (class "Default")
      (node (ref "D13") (pin "2") (pinfunction "D_2") (pintype "passive"))
    )
    (net (code "91") (name "unconnected-(D13-DP-Pad5)") (class "Default")
      (node (ref "D13") (pin "5") (pinfunction "DP_5") (pintype "passive"))
    )
    (net (code "92") (name "unconnected-(D13-E-Pad1)") (class "Default")
      (node (ref "D13") (pin "1") (pinfunction "E_1") (pintype "passive"))
    )
    (net (code "93") (name "unconnected-(D13-F-Pad9)") (class "Default")
      (node (ref "D13") (pin "9") (pinfunction "F_9") (pintype "passive"))
    )
    (net (code "94") (name "unconnected-(D13-G-Pad10)") (class "Default")
      (node (ref "D13") (pin "10") (pinfunction "G_10") (pintype "passive"))
    )
    (net (code "95") (name "unconnected-(IC1-GPB5-Pad6)") (class "Default")
      (node (ref "IC1") (pin "6") (pinfunction "GPB5_6") (pintype "bidirectional"))
    )
    (net (code "96") (name "unconnected-(IC1-GPB6-Pad7)") (class "Default")
      (node (ref "IC1") (pin "7") (pinfunction "GPB6_7") (pintype "bidirectional"))
    )
    (net (code "97") (name "unconnected-(IC1-GPB7-Pad8)") (class "Default")
      (node (ref "IC1") (pin "8") (pinfunction "GPB7_8") (pintype "bidirectional"))
    )
    (net (code "98") (name "unconnected-(IC1-INTA-Pad20)") (class "Default")
      (node (ref "IC1") (pin "20") (pinfunction "INTA_20") (pintype "output"))
    )
    (net (code "99") (name "unconnected-(IC1-INTB-Pad19)") (class "Default")
      (node (ref "IC1") (pin "19") (pinfunction "INTB_19") (pintype "output"))
    )
    (net (code "100") (name "unconnected-(U1-OUT12-Pad14)") (class "Default")
      (node (ref "U1") (pin "14") (pinfunction "OUT12_14") (pintype "bidirectional"))
    )
    (net (code "101") (name "unconnected-(U1-OUT13-Pad15)") (class "Default")
      (node (ref "U1") (pin "15") (pinfunction "OUT13_15") (pintype "bidirectional"))
    )
    (net (code "102") (name "unconnected-(U1-OUT14-Pad16)") (class "Default")
      (node (ref "U1") (pin "16") (pinfunction "OUT14_16") (pintype "bidirectional"))
    )
    (net (code "103") (name "unconnected-(U1-OUT15-Pad17)") (class "Default")
      (node (ref "U1") (pin "17") (pinfunction "OUT15_17") (pintype "bidirectional"))
    )
    (net (code "104") (name "unconnected-(U1-SOUT-Pad19)") (class "Default")
      (node (ref "U1") (pin "19") (pinfunction "SOUT_19") (pintype "bidirectional"))
    )
  )
)
